# StreamDeck_alimentacion-V0.net
KiCad netlist of a schematic drawn in Altium Designer
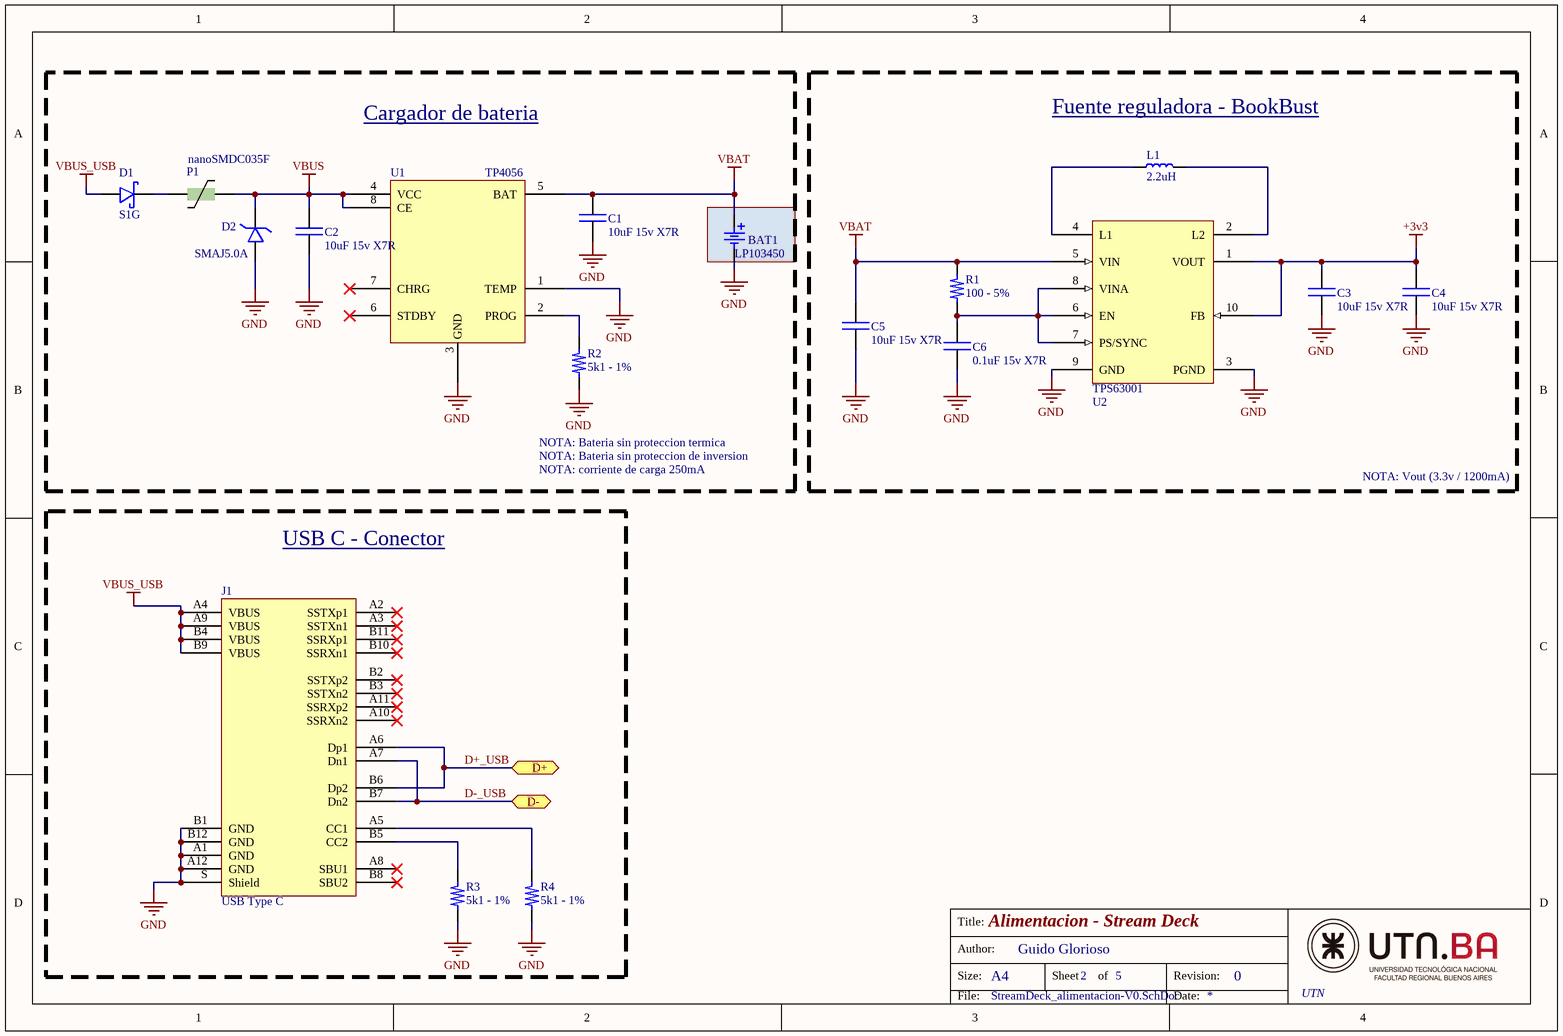
[diagram p0: StreamDeck_alimentacion-V0.SchDoc]

(export (version "E")
  (design (tool "Eeschema 10.0.6"))
  (components
    (comp (ref "BAT1")
      (value "LP103450")
      (footprint "BAT-PAD-CONECTOR")
      (libsource (lib "StreamDeck-V0") (part "LP103450"))
    )
    (comp (ref "C1")
      (value "10uF 15v X7R")
      (footprint "C_0805")
      (description "Capacitor no polarizado")
      (libsource (lib "StreamDeck-V0") (part "Capacitor NP"))
    )
    (comp (ref "C2")
      (value "10uF 15v X7R")
      (footprint "C_1206")
      (description "Capacitor no polarizado")
      (libsource (lib "StreamDeck-V0") (part "Capacitor NP"))
    )
    (comp (ref "C3")
      (value "10uF 15v X7R")
      (footprint "C_0805")
      (description "Capacitor no polarizado")
      (libsource (lib "StreamDeck-V0") (part "Capacitor NP"))
    )
    (comp (ref "C4")
      (value "10uF 15v X7R")
      (footprint "C_0805")
      (description "Capacitor no polarizado")
      (libsource (lib "StreamDeck-V0") (part "Capacitor NP"))
    )
    (comp (ref "C5")
      (value "10uF 15v X7R")
      (footprint "C_0805")
      (description "Capacitor no polarizado")
      (libsource (lib "StreamDeck-V0") (part "Capacitor NP"))
    )
    (comp (ref "C6")
      (value "0.1uF 15v X7R")
      (footprint "C_0805")
      (description "Capacitor no polarizado")
      (libsource (lib "StreamDeck-V0") (part "Capacitor NP"))
    )
    (comp (ref "D1")
      (value "S1G")
      (footprint "D_SMA")
      (description "Diodo Schottky")
      (libsource (lib "StreamDeck-V0") (part "Diodo Schottky"))
    )
    (comp (ref "D2")
      (value "SMAJ5.0A")
      (footprint "D_SMA")
      (description "Diodo TVS")
      (libsource (lib "StreamDeck-V0") (part "Diodo TVS"))
    )
    (comp (ref "J1")
      (value "USB Type C")
      (footprint "USB-C")
      (description "Conector USB C 3.0")
      (libsource (lib "StreamDeck-V0") (part "USB-C"))
    )
    (comp (ref "L1")
      (value "2.2uH")
      (footprint "LQH44")
      (description "Inductor - SMD LQH44 - 1Amp")
      (libsource (lib "StreamDeck-V0") (part "Inductor"))
    )
    (comp (ref "P1")
      (value "nanoSMDC035F")
      (footprint "NANOSMDC")
      (description "Poly Switch")
      (libsource (lib "StreamDeck-V0") (part "Poly Switch"))
    )
    (comp (ref "R1")
      (value "100 - 5%")
      (footprint "R_0805")
      (description "Resistor")
      (libsource (lib "StreamDeck-V0") (part "Resistor"))
    )
    (comp (ref "R2")
      (value "5k1 - 1%")
      (footprint "R_0805")
      (description "Resistor")
      (libsource (lib "StreamDeck-V0") (part "Resistor"))
    )
    (comp (ref "R3")
      (value "5k1 - 1%")
      (footprint "R_0805")
      (description "Resistor")
      (libsource (lib "StreamDeck-V0") (part "Resistor"))
    )
    (comp (ref "R4")
      (value "5k1 - 1%")
      (footprint "R_0805")
      (description "Resistor")
      (libsource (lib "StreamDeck-V0") (part "Resistor"))
    )
    (comp (ref "U1")
      (value "TP4056")
      (footprint "SOP8 - IPC")
      (description "Standalone Linear Li-lon Battery Charger with Thermal Regulation in SOP-8")
      (libsource (lib "StreamDeck-V0") (part "TP4056"))
    )
    (comp (ref "U2")
      (value "TPS63001")
      (footprint "VSON - 10")
      (description "High-Efficient Single Inductor Buck-Boost Converter With 1.8-A Switches")
      (libsource (lib "StreamDeck-V0") (part "TPS63001"))
    )
  )
  (nets
    (net (code "1") (name "+3v3") (class "Default")
      (node (ref "C3") (pin "1") (pinfunction "1_1") (pintype "passive"))
      (node (ref "C4") (pin "1") (pinfunction "1_1") (pintype "passive"))
      (node (ref "U2") (pin "1") (pinfunction "VOUT_1") (pintype "power_in"))
      (node (ref "U2") (pin "10") (pinfunction "FB_10") (pintype "input"))
    )
    (net (code "2") (name "/D+_USB") (class "Default")
      (node (ref "J1") (pin "A6") (pinfunction "Dp1_A6") (pintype "passive"))
      (node (ref "J1") (pin "B6") (pinfunction "Dp2_B6") (pintype "passive"))
    )
    (net (code "3") (name "/D-_USB") (class "Default")
      (node (ref "J1") (pin "A7") (pinfunction "Dn1_A7") (pintype "passive"))
      (node (ref "J1") (pin "B7") (pinfunction "Dn2_B7") (pintype "passive"))
    )
    (net (code "4") (name "GND") (class "Default")
      (node (ref "BAT1") (pin "2") (pintype "passive"))
      (node (ref "C1") (pin "2") (pinfunction "2_2") (pintype "passive"))
      (node (ref "C2") (pin "2") (pinfunction "2_2") (pintype "passive"))
      (node (ref "C3") (pin "2") (pinfunction "2_2") (pintype "passive"))
      (node (ref "C4") (pin "2") (pinfunction "2_2") (pintype "passive"))
      (node (ref "C5") (pin "2") (pinfunction "2_2") (pintype "passive"))
      (node (ref "C6") (pin "2") (pinfunction "2_2") (pintype "passive"))
      (node (ref "D2") (pin "1") (pinfunction "anodo_1") (pintype "passive"))
      (node (ref "J1") (pin "A1") (pinfunction "GND_A1") (pintype "passive"))
      (node (ref "J1") (pin "A12") (pinfunction "GND_A12") (pintype "passive"))
      (node (ref "J1") (pin "B1") (pinfunction "GND_B1") (pintype "passive"))
      (node (ref "J1") (pin "B12") (pinfunction "GND_B12") (pintype "passive"))
      (node (ref "J1") (pin "S") (pinfunction "Shield_S") (pintype "passive"))
      (node (ref "R2") (pin "1") (pinfunction "1_1") (pintype "passive"))
      (node (ref "R3") (pin "1") (pinfunction "1_1") (pintype "passive"))
      (node (ref "R4") (pin "1") (pinfunction "1_1") (pintype "passive"))
      (node (ref "U1") (pin "1") (pinfunction "TEMP_1") (pintype "passive"))
      (node (ref "U1") (pin "3") (pinfunction "GND_3") (pintype "power_in"))
      (node (ref "U2") (pin "3") (pinfunction "PGND_3") (pintype "power_in"))
      (node (ref "U2") (pin "9") (pinfunction "GND_9") (pintype "power_in"))
    )
    (net (code "5") (name "Net-(D1-Pad2)") (class "Default")
      (node (ref "D1") (pin "2") (pinfunction "2_2") (pintype "passive"))
      (node (ref "P1") (pin "1") (pinfunction "1_1") (pintype "power_in"))
    )
    (net (code "6") (name "Net-(J1-CC1)") (class "Default")
      (node (ref "J1") (pin "A5") (pinfunction "CC1_A5") (pintype "passive"))
      (node (ref "R4") (pin "2") (pinfunction "2_2") (pintype "passive"))
    )
    (net (code "7") (name "Net-(J1-CC2)") (class "Default")
      (node (ref "J1") (pin "B5") (pinfunction "CC2_B5") (pintype "passive"))
      (node (ref "R3") (pin "2") (pinfunction "2_2") (pintype "passive"))
    )
    (net (code "8") (name "Net-(U1-PROG)") (class "Default")
      (node (ref "R2") (pin "2") (pinfunction "2_2") (pintype "passive"))
      (node (ref "U1") (pin "2") (pinfunction "PROG_2") (pintype "passive"))
    )
    (net (code "9") (name "Net-(U2-EN)") (class "Default")
      (node (ref "C6") (pin "1") (pinfunction "1_1") (pintype "passive"))
      (node (ref "R1") (pin "1") (pinfunction "1_1") (pintype "passive"))
      (node (ref "U2") (pin "6") (pinfunction "EN_6") (pintype "input"))
      (node (ref "U2") (pin "7") (pinfunction "PS/SYNC_7") (pintype "input"))
      (node (ref "U2") (pin "8") (pinfunction "VINA_8") (pintype "input"))
    )
    (net (code "10") (name "Net-(U2-L1)") (class "Default")
      (node (ref "L1") (pin "1") (pinfunction "1_1") (pintype "passive"))
      (node (ref "U2") (pin "4") (pinfunction "L1_4") (pintype "passive"))
    )
    (net (code "11") (name "Net-(U2-L2)") (class "Default")
      (node (ref "L1") (pin "2") (pinfunction "2_2") (pintype "passive"))
      (node (ref "U2") (pin "2") (pinfunction "L2_2") (pintype "passive"))
    )
    (net (code "12") (name "VBAT") (class "Default")
      (node (ref "BAT1") (pin "1") (pintype "passive"))
      (node (ref "C1") (pin "1") (pinfunction "1_1") (pintype "passive"))
      (node (ref "C5") (pin "1") (pinfunction "1_1") (pintype "passive"))
      (node (ref "R1") (pin "2") (pinfunction "2_2") (pintype "passive"))
      (node (ref "U1") (pin "5") (pinfunction "BAT_5") (pintype "power_in"))
      (node (ref "U2") (pin "5") (pinfunction "VIN_5") (pintype "input"))
    )
    (net (code "13") (name "VBUS") (class "Default")
      (node (ref "C2") (pin "1") (pinfunction "1_1") (pintype "passive"))
      (node (ref "D2") (pin "2") (pinfunction "catodo_2") (pintype "passive"))
      (node (ref "P1") (pin "2") (pinfunction "2_2") (pintype "power_in"))
      (node (ref "U1") (pin "4") (pinfunction "VCC_4") (pintype "power_in"))
      (node (ref "U1") (pin "8") (pinfunction "CE_8") (pintype "passive"))
    )
    (net (code "14") (name "VBUS_USB") (class "Default")
      (node (ref "D1") (pin "1") (pinfunction "anodo_1") (pintype "passive"))
      (node (ref "J1") (pin "A4") (pinfunction "VBUS_A4") (pintype "passive"))
      (node (ref "J1") (pin "A9") (pinfunction "VBUS_A9") (pintype "passive"))
      (node (ref "J1") (pin "B4") (pinfunction "VBUS_B4") (pintype "passive"))
      (node (ref "J1") (pin "B9") (pinfunction "VBUS_B9") (pintype "passive"))
    )
    (net (code "15") (name "unconnected-(J1-SBU1-PadA8)") (class "Default")
      (node (ref "J1") (pin "A8") (pinfunction "SBU1_A8") (pintype "passive+no_connect"))
    )
    (net (code "16") (name "unconnected-(J1-SBU2-PadB8)") (class "Default")
      (node (ref "J1") (pin "B8") (pinfunction "SBU2_B8") (pintype "passive+no_connect"))
    )
    (net (code "17") (name "unconnected-(J1-SSRXn1-PadB10)") (class "Default")
      (node (ref "J1") (pin "B10") (pinfunction "SSRXn1_B10") (pintype "passive+no_connect"))
    )
    (net (code "18") (name "unconnected-(J1-SSRXn2-PadA10)") (class "Default")
      (node (ref "J1") (pin "A10") (pinfunction "SSRXn2_A10") (pintype "passive+no_connect"))
    )
    (net (code "19") (name "unconnected-(J1-SSRXp1-PadB11)") (class "Default")
      (node (ref "J1") (pin "B11") (pinfunction "SSRXp1_B11") (pintype "passive+no_connect"))
    )
    (net (code "20") (name "unconnected-(J1-SSRXp2-PadA11)") (class "Default")
      (node (ref "J1") (pin "A11") (pinfunction "SSRXp2_A11") (pintype "passive+no_connect"))
    )
    (net (code "21") (name "unconnected-(J1-SSTXn1-PadA3)") (class "Default")
      (node (ref "J1") (pin "A3") (pinfunction "SSTXn1_A3") (pintype "passive+no_connect"))
    )
    (net (code "22") (name "unconnected-(J1-SSTXn2-PadB3)") (class "Default")
      (node (ref "J1") (pin "B3") (pinfunction "SSTXn2_B3") (pintype "passive+no_connect"))
    )
    (net (code "23") (name "unconnected-(J1-SSTXp1-PadA2)") (class "Default")
      (node (ref "J1") (pin "A2") (pinfunction "SSTXp1_A2") (pintype "passive+no_connect"))
    )
    (net (code "24") (name "unconnected-(J1-SSTXp2-PadB2)") (class "Default")
      (node (ref "J1") (pin "B2") (pinfunction "SSTXp2_B2") (pintype "passive+no_connect"))
    )
    (net (code "25") (name "unconnected-(U1-CHRG-Pad7)") (class "Default")
      (node (ref "U1") (pin "7") (pinfunction "CHRG_7") (pintype "passive+no_connect"))
    )
    (net (code "26") (name "unconnected-(U1-STDBY-Pad6)") (class "Default")
      (node (ref "U1") (pin "6") (pinfunction "STDBY_6") (pintype "passive+no_connect"))
    )
  )
)
